# MSW_V4_LienDong.net
KiCad netlist of a schematic drawn in Altium Designer
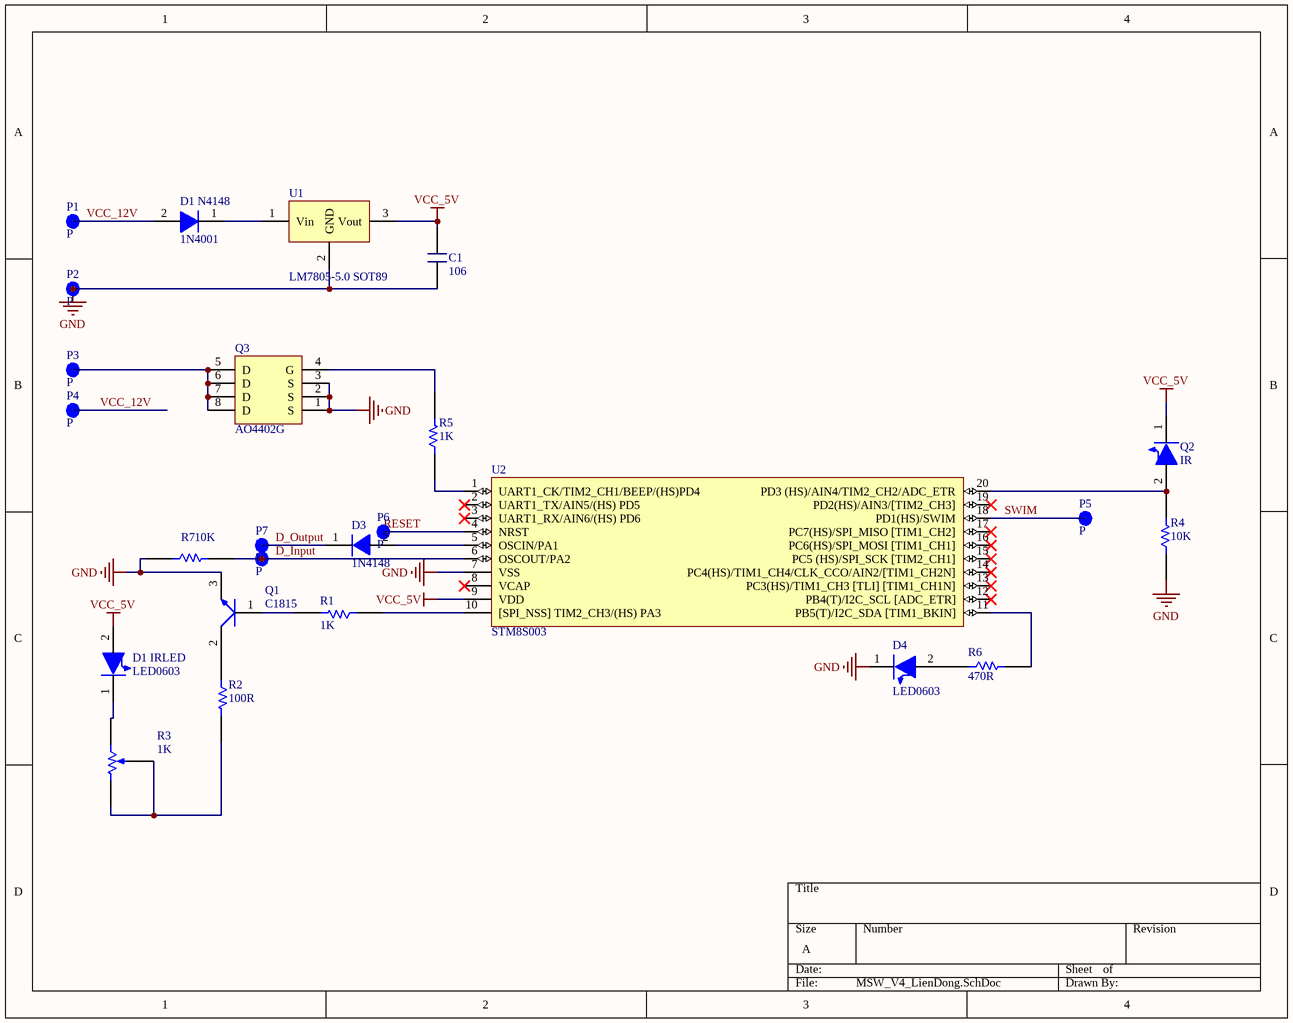
[diagram p0: MSW_V4_LienDong.SchDoc]

(export (version "E")
  (design (tool "Eeschema 10.0.6"))
  (components
    (comp (ref "C1") (value "106") (libsource (lib "Integrated_Library1") (part "Capacitor 106")))
    (comp (ref "D1 IRLED")
      (value "LED0603")
      (footprint "DIOC1608X06N")
      (libsource (lib "Integrated_Library1") (part "LED0603"))
    )
    (comp (ref "D1 N4148")
      (value "1N4001")
      (footprint "SODFL504X244-2N")
      (description "1N4007_SMD")
      (libsource (lib "Integrated_Library1") (part "1N4007_SMD Diode"))
    )
    (comp (ref "D3")
      (value "1N4148")
      (footprint "DIOMELF3515N")
      (description "DIODE GEN PURP 75V 200MA DO213AA")
      (libsource (lib "Integrated_Library1") (part "1N4148_SMD"))
    )
    (comp (ref "D4")
      (value "LED0603")
      (footprint "DIOC1608X06N")
      (libsource (lib "Integrated_Library1") (part "LED0603"))
    )
    (comp (ref "P1") (value "P") (libsource (lib "Integrated_Library1") (part "Point")))
    (comp (ref "P2") (value "P") (libsource (lib "Integrated_Library1") (part "Point")))
    (comp (ref "P3") (value "P") (libsource (lib "Integrated_Library1") (part "Point")))
    (comp (ref "P4") (value "P") (libsource (lib "Integrated_Library1") (part "Point")))
    (comp (ref "P5") (value "P") (libsource (lib "Integrated_Library1") (part "Point")))
    (comp (ref "P6") (value "P") (libsource (lib "Integrated_Library1") (part "Point")))
    (comp (ref "P7") (value "P") (libsource (lib "Integrated_Library1") (part "Point")))
    (comp (ref "P8") (value "P") (libsource (lib "Integrated_Library1") (part "Point")))
    (comp (ref "Q1")
      (value "C1815")
      (footprint "SOT95P278X125-3N")
      (description "SOT-23 Plastic-Encapsulate Transistors")
      (libsource (lib "Integrated_Library1") (part "Transitor C1815 NPN"))
    )
    (comp (ref "Q2")
      (value "IR")
      (footprint "DIOC1608X06N")
      (description "LED0603")
      (libsource (lib "Integrated_Library1") (part "LED0603"))
    )
    (comp (ref "Q3")
      (value "AO4402G")
      (description "20V N-Channel MOSFET")
      (libsource (lib "Integrated_Library1") (part "AO4402G"))
    )
    (comp (ref "R1")
      (value "1K")
      (footprint "RESC2608X06N_0603")
      (description "Thick Film Resistors - SMD 0603 1kOHMS 5% 1/10WATT")
      (libsource (lib "Integrated_Library1") (part "1k_0603_5%"))
    )
    (comp (ref "R2")
      (value "100R")
      (footprint "RESC2608X06N_0603")
      (description "Thick Film Resistors - SMD 0603 100OHMS 5% 1/10WATT")
      (libsource (lib "Integrated_Library1") (part "R100_0603_5%"))
    )
    (comp (ref "R3")
      (value "1K")
      (footprint "Var_SMD_3x3")
      (description "Varistor 3x3 SMD 1KOhm 5% 1/10WATT")
      (libsource (lib "Integrated_Library1") (part "Varistor 3x3 SMD 1KOhm"))
    )
    (comp (ref "R4")
      (value "10K")
      (footprint "RESC2608X06N_0603")
      (description "RES SMD 10K OHM 1% 1/4W 0603")
      (libsource (lib "Integrated_Library1") (part "R10k_0603_5%"))
    )
    (comp (ref "R5")
      (value "1K")
      (footprint "RESC2608X06N_0603")
      (description "Thick Film Resistors - SMD 0603 1kOHMS 5% 1/10WATT")
      (libsource (lib "Integrated_Library1") (part "1k_0603_5%"))
    )
    (comp (ref "R6")
      (value "470R")
      (footprint "RESC2608X06N_0603")
      (description "Thick Film Resistors - SMD 470 ohm 5%")
      (libsource (lib "Integrated_Library1") (part "R470_0603_5%"))
    )
    (comp (ref "R7")
      (value "10K")
      (footprint "RESC2608X06N_0603")
      (description "RES SMD 10K OHM 1% 1/4W 0603")
      (libsource (lib "Integrated_Library1") (part "R10k_0603_5%"))
    )
    (comp (ref "U1")
      (value "LM7805-5.0 SOT89")
      (footprint "SOT89-150P409X160-3N")
      (description "LM7805 SOT89")
      (libsource (lib "Integrated_Library1") (part "LM7805 SOT89"))
    )
    (comp (ref "U2")
      (value "STM8S003")
      (footprint "TSOP65P640X120-20N")
      (description "MCU 8-bit STM8S STM8 CISC 8KB Flash 3.3V/5V 20-Pin TSSOP T/R")
      (libsource (lib "Integrated_Library1") (part "STM8S003"))
    )
  )
  (nets
    (net (code "1") (name "/D_Input") (class "Default")
      (node (ref "P8") (pin "1") (pinfunction "1_1") (pintype "passive"))
      (node (ref "R7") (pin "2") (pinfunction "2_2") (pintype "passive"))
      (node (ref "U2") (pin "6") (pinfunction "OSCOUT/PA2_6") (pintype "bidirectional"))
    )
    (net (code "2") (name "/D_Output") (class "Default")
      (node (ref "D3") (pin "1") (pinfunction "C_1") (pintype "passive"))
      (node (ref "P7") (pin "1") (pinfunction "1_1") (pintype "passive"))
    )
    (net (code "3") (name "/RESET") (class "Default")
      (node (ref "P6") (pin "1") (pinfunction "1_1") (pintype "passive"))
      (node (ref "U2") (pin "4") (pinfunction "NRST_4") (pintype "bidirectional"))
    )
    (net (code "4") (name "/SWIM") (class "Default")
      (node (ref "P5") (pin "1") (pinfunction "1_1") (pintype "passive"))
      (node (ref "U2") (pin "18") (pinfunction "PD1(HS)/SWIM_18") (pintype "bidirectional"))
    )
    (net (code "5") (name "/VCC_12V") (class "Default")
      (node (ref "D1 N4148") (pin "2") (pinfunction "A_2") (pintype "passive"))
      (node (ref "P1") (pin "1") (pinfunction "1_1") (pintype "passive"))
      (node (ref "P4") (pin "1") (pinfunction "1_1") (pintype "passive"))
    )
    (net (code "6") (name "GND") (class "Default")
      (node (ref "C1") (pin "1") (pinfunction "1_1") (pintype "passive"))
      (node (ref "P2") (pin "1") (pinfunction "1_1") (pintype "passive"))
      (node (ref "Q1") (pin "3") (pinfunction "E_3") (pintype "passive"))
      (node (ref "Q3") (pin "1") (pinfunction "S_1") (pintype "passive"))
      (node (ref "Q3") (pin "2") (pinfunction "S_2") (pintype "passive"))
      (node (ref "Q3") (pin "3") (pinfunction "S_3") (pintype "passive"))
      (node (ref "R4") (pin "1") (pinfunction "1_1") (pintype "passive"))
      (node (ref "R7") (pin "1") (pinfunction "1_1") (pintype "passive"))
      (node (ref "U1") (pin "2") (pinfunction "GND_2") (pintype "power_in"))
      (node (ref "U2") (pin "7") (pinfunction "VSS_7") (pintype "power_in"))
    )
    (net (code "7") (name "Net-(D1 IRLED-A)") (class "Default")
      (node (ref "D1 IRLED") (pin "1") (pinfunction "A_1") (pintype "passive"))
      (node (ref "R3") (pin "1") (pinfunction "1_1") (pintype "passive"))
    )
    (net (code "8") (name "Net-(D1 N4148-C)") (class "Default")
      (node (ref "D1 N4148") (pin "1") (pinfunction "C_1") (pintype "passive"))
      (node (ref "U1") (pin "1") (pinfunction "Vin_1") (pintype "power_in"))
    )
    (net (code "9") (name "Net-(D3-A)") (class "Default")
      (node (ref "D3") (pin "2") (pinfunction "A_2") (pintype "passive"))
      (node (ref "U2") (pin "5") (pinfunction "OSCIN/PA1_5") (pintype "bidirectional"))
    )
    (net (code "10") (name "Net-(D4-C)") (class "Default")
      (node (ref "D4") (pin "2") (pinfunction "C_2") (pintype "passive"))
      (node (ref "R6") (pin "1") (pinfunction "1_1") (pintype "passive"))
    )
    (net (code "11") (name "Net-(P3-Pad1)") (class "Default")
      (node (ref "P3") (pin "1") (pinfunction "1_1") (pintype "passive"))
      (node (ref "Q3") (pin "5") (pinfunction "D_5") (pintype "passive"))
      (node (ref "Q3") (pin "6") (pinfunction "D_6") (pintype "passive"))
      (node (ref "Q3") (pin "7") (pinfunction "D_7") (pintype "passive"))
      (node (ref "Q3") (pin "8") (pinfunction "D_8") (pintype "passive"))
    )
    (net (code "12") (name "Net-(Q1-B)") (class "Default")
      (node (ref "Q1") (pin "1") (pinfunction "B_1") (pintype "passive"))
      (node (ref "R1") (pin "2") (pinfunction "2_2") (pintype "passive"))
    )
    (net (code "13") (name "Net-(Q1-C)") (class "Default")
      (node (ref "Q1") (pin "2") (pinfunction "C_2") (pintype "passive"))
      (node (ref "R2") (pin "1") (pinfunction "1_1") (pintype "passive"))
    )
    (net (code "14") (name "Net-(Q2-C)") (class "Default")
      (node (ref "Q2") (pin "2") (pinfunction "C_2") (pintype "passive"))
      (node (ref "R4") (pin "2") (pinfunction "2_2") (pintype "passive"))
      (node (ref "U2") (pin "20") (pinfunction "PD3_(HS)/AIN4/TIM2_CH2/ADC_ETR_20") (pintype "bidirectional"))
    )
    (net (code "15") (name "Net-(Q3-G)") (class "Default")
      (node (ref "Q3") (pin "4") (pinfunction "G_4") (pintype "passive"))
      (node (ref "R5") (pin "2") (pinfunction "2_2") (pintype "passive"))
    )
    (net (code "16") (name "Net-(R2-Pad2)") (class "Default")
      (node (ref "R2") (pin "2") (pinfunction "2_2") (pintype "passive"))
      (node (ref "R3") (pin "2") (pinfunction "2_2") (pintype "passive"))
      (node (ref "R3") (pin "3") (pinfunction "3_3") (pintype "passive"))
    )
    (net (code "17") (name "Net-(U2-PB5(T){slash}I2C_SDA_[TIM1_BKIN])") (class "Default")
      (node (ref "R6") (pin "2") (pinfunction "2_2") (pintype "passive"))
      (node (ref "U2") (pin "11") (pinfunction "PB5(T)/I2C_SDA_[TIM1_BKIN]_11") (pintype "bidirectional"))
    )
    (net (code "18") (name "Net-(U2-UART1_CK{slash}TIM2_CH1{slash}BEEP{slash}(HS)PD4)") (class "Default")
      (node (ref "R5") (pin "1") (pinfunction "1_1") (pintype "passive"))
      (node (ref "U2") (pin "1") (pinfunction "UART1_CK/TIM2_CH1/BEEP/(HS)PD4_1") (pintype "bidirectional"))
    )
    (net (code "19") (name "Net-(U2-[SPI_NSS]_TIM2_CH3{slash}(HS)_PA3)") (class "Default")
      (node (ref "R1") (pin "1") (pinfunction "1_1") (pintype "passive"))
      (node (ref "U2") (pin "10") (pinfunction "[SPI_NSS]_TIM2_CH3/(HS)_PA3_10") (pintype "power_in"))
    )
    (net (code "20") (name "VCC_5V") (class "Default")
      (node (ref "C1") (pin "2") (pinfunction "2_2") (pintype "passive"))
      (node (ref "D1 IRLED") (pin "2") (pinfunction "C_2") (pintype "passive"))
      (node (ref "Q2") (pin "1") (pinfunction "A_1") (pintype "passive"))
      (node (ref "U1") (pin "3") (pinfunction "Vout_3") (pintype "power_in"))
      (node (ref "U2") (pin "9") (pinfunction "VDD_9") (pintype "power_in"))
    )
    (net (code "21") (name "unconnected-(D4-A-Pad1)") (class "Default")
      (node (ref "D4") (pin "1") (pinfunction "A_1") (pintype "passive"))
    )
    (net (code "22") (name "unconnected-(U2-PB4(T){slash}I2C_SCL_[ADC_ETR]-Pad12)") (class "Default")
      (node (ref "U2") (pin "12") (pinfunction "PB4(T)/I2C_SCL_[ADC_ETR]_12") (pintype "bidirectional+no_connect"))
    )
    (net (code "23") (name "unconnected-(U2-PC3(HS){slash}TIM1_CH3_[TLI]_[TIM1_CH1N]-Pad13)") (class "Default")
      (node (ref "U2") (pin "13") (pinfunction "PC3(HS)/TIM1_CH3_[TLI]_[TIM1_CH1N]_13") (pintype "bidirectional+no_connect"))
    )
    (net (code "24") (name "unconnected-(U2-PC4(HS){slash}TIM1_CH4{slash}CLK_CCO{slash}AIN2{slash}[TIM1_CH2N]-Pad14)") (class "Default")
      (node (ref "U2") (pin "14") (pinfunction "PC4(HS)/TIM1_CH4/CLK_CCO/AIN2/[TIM1_CH2N]_14") (pintype "bidirectional+no_connect"))
    )
    (net (code "25") (name "unconnected-(U2-PC5_(HS){slash}SPI_SCK_[TIM2_CH1]-Pad15)") (class "Default")
      (node (ref "U2") (pin "15") (pinfunction "PC5_(HS)/SPI_SCK_[TIM2_CH1]_15") (pintype "bidirectional+no_connect"))
    )
    (net (code "26") (name "unconnected-(U2-PC6(HS){slash}SPI_MOSI_[TIM1_CH1]-Pad16)") (class "Default")
      (node (ref "U2") (pin "16") (pinfunction "PC6(HS)/SPI_MOSI_[TIM1_CH1]_16") (pintype "bidirectional+no_connect"))
    )
    (net (code "27") (name "unconnected-(U2-PC7(HS){slash}SPI_MISO_[TIM1_CH2]-Pad17)") (class "Default")
      (node (ref "U2") (pin "17") (pinfunction "PC7(HS)/SPI_MISO_[TIM1_CH2]_17") (pintype "bidirectional+no_connect"))
    )
    (net (code "28") (name "unconnected-(U2-PD2(HS){slash}AIN3{slash}[TIM2_CH3]-Pad19)") (class "Default")
      (node (ref "U2") (pin "19") (pinfunction "PD2(HS)/AIN3/[TIM2_CH3]_19") (pintype "bidirectional+no_connect"))
    )
    (net (code "29") (name "unconnected-(U2-UART1_RX{slash}AIN6{slash}(HS)_PD6-Pad3)") (class "Default")
      (node (ref "U2") (pin "3") (pinfunction "UART1_RX/AIN6/(HS)_PD6_3") (pintype "bidirectional+no_connect"))
    )
    (net (code "30") (name "unconnected-(U2-UART1_TX{slash}AIN5{slash}(HS)_PD5-Pad2)") (class "Default")
      (node (ref "U2") (pin "2") (pinfunction "UART1_TX/AIN5/(HS)_PD5_2") (pintype "bidirectional+no_connect"))
    )
    (net (code "31") (name "unconnected-(U2-VCAP-Pad8)") (class "Default")
      (node (ref "U2") (pin "8") (pinfunction "VCAP_8") (pintype "power_in+no_connect"))
    )
  )
)
